# 1-Schematic_petdaktil.net
KiCad netlist of a schematic drawn in EasyEDA
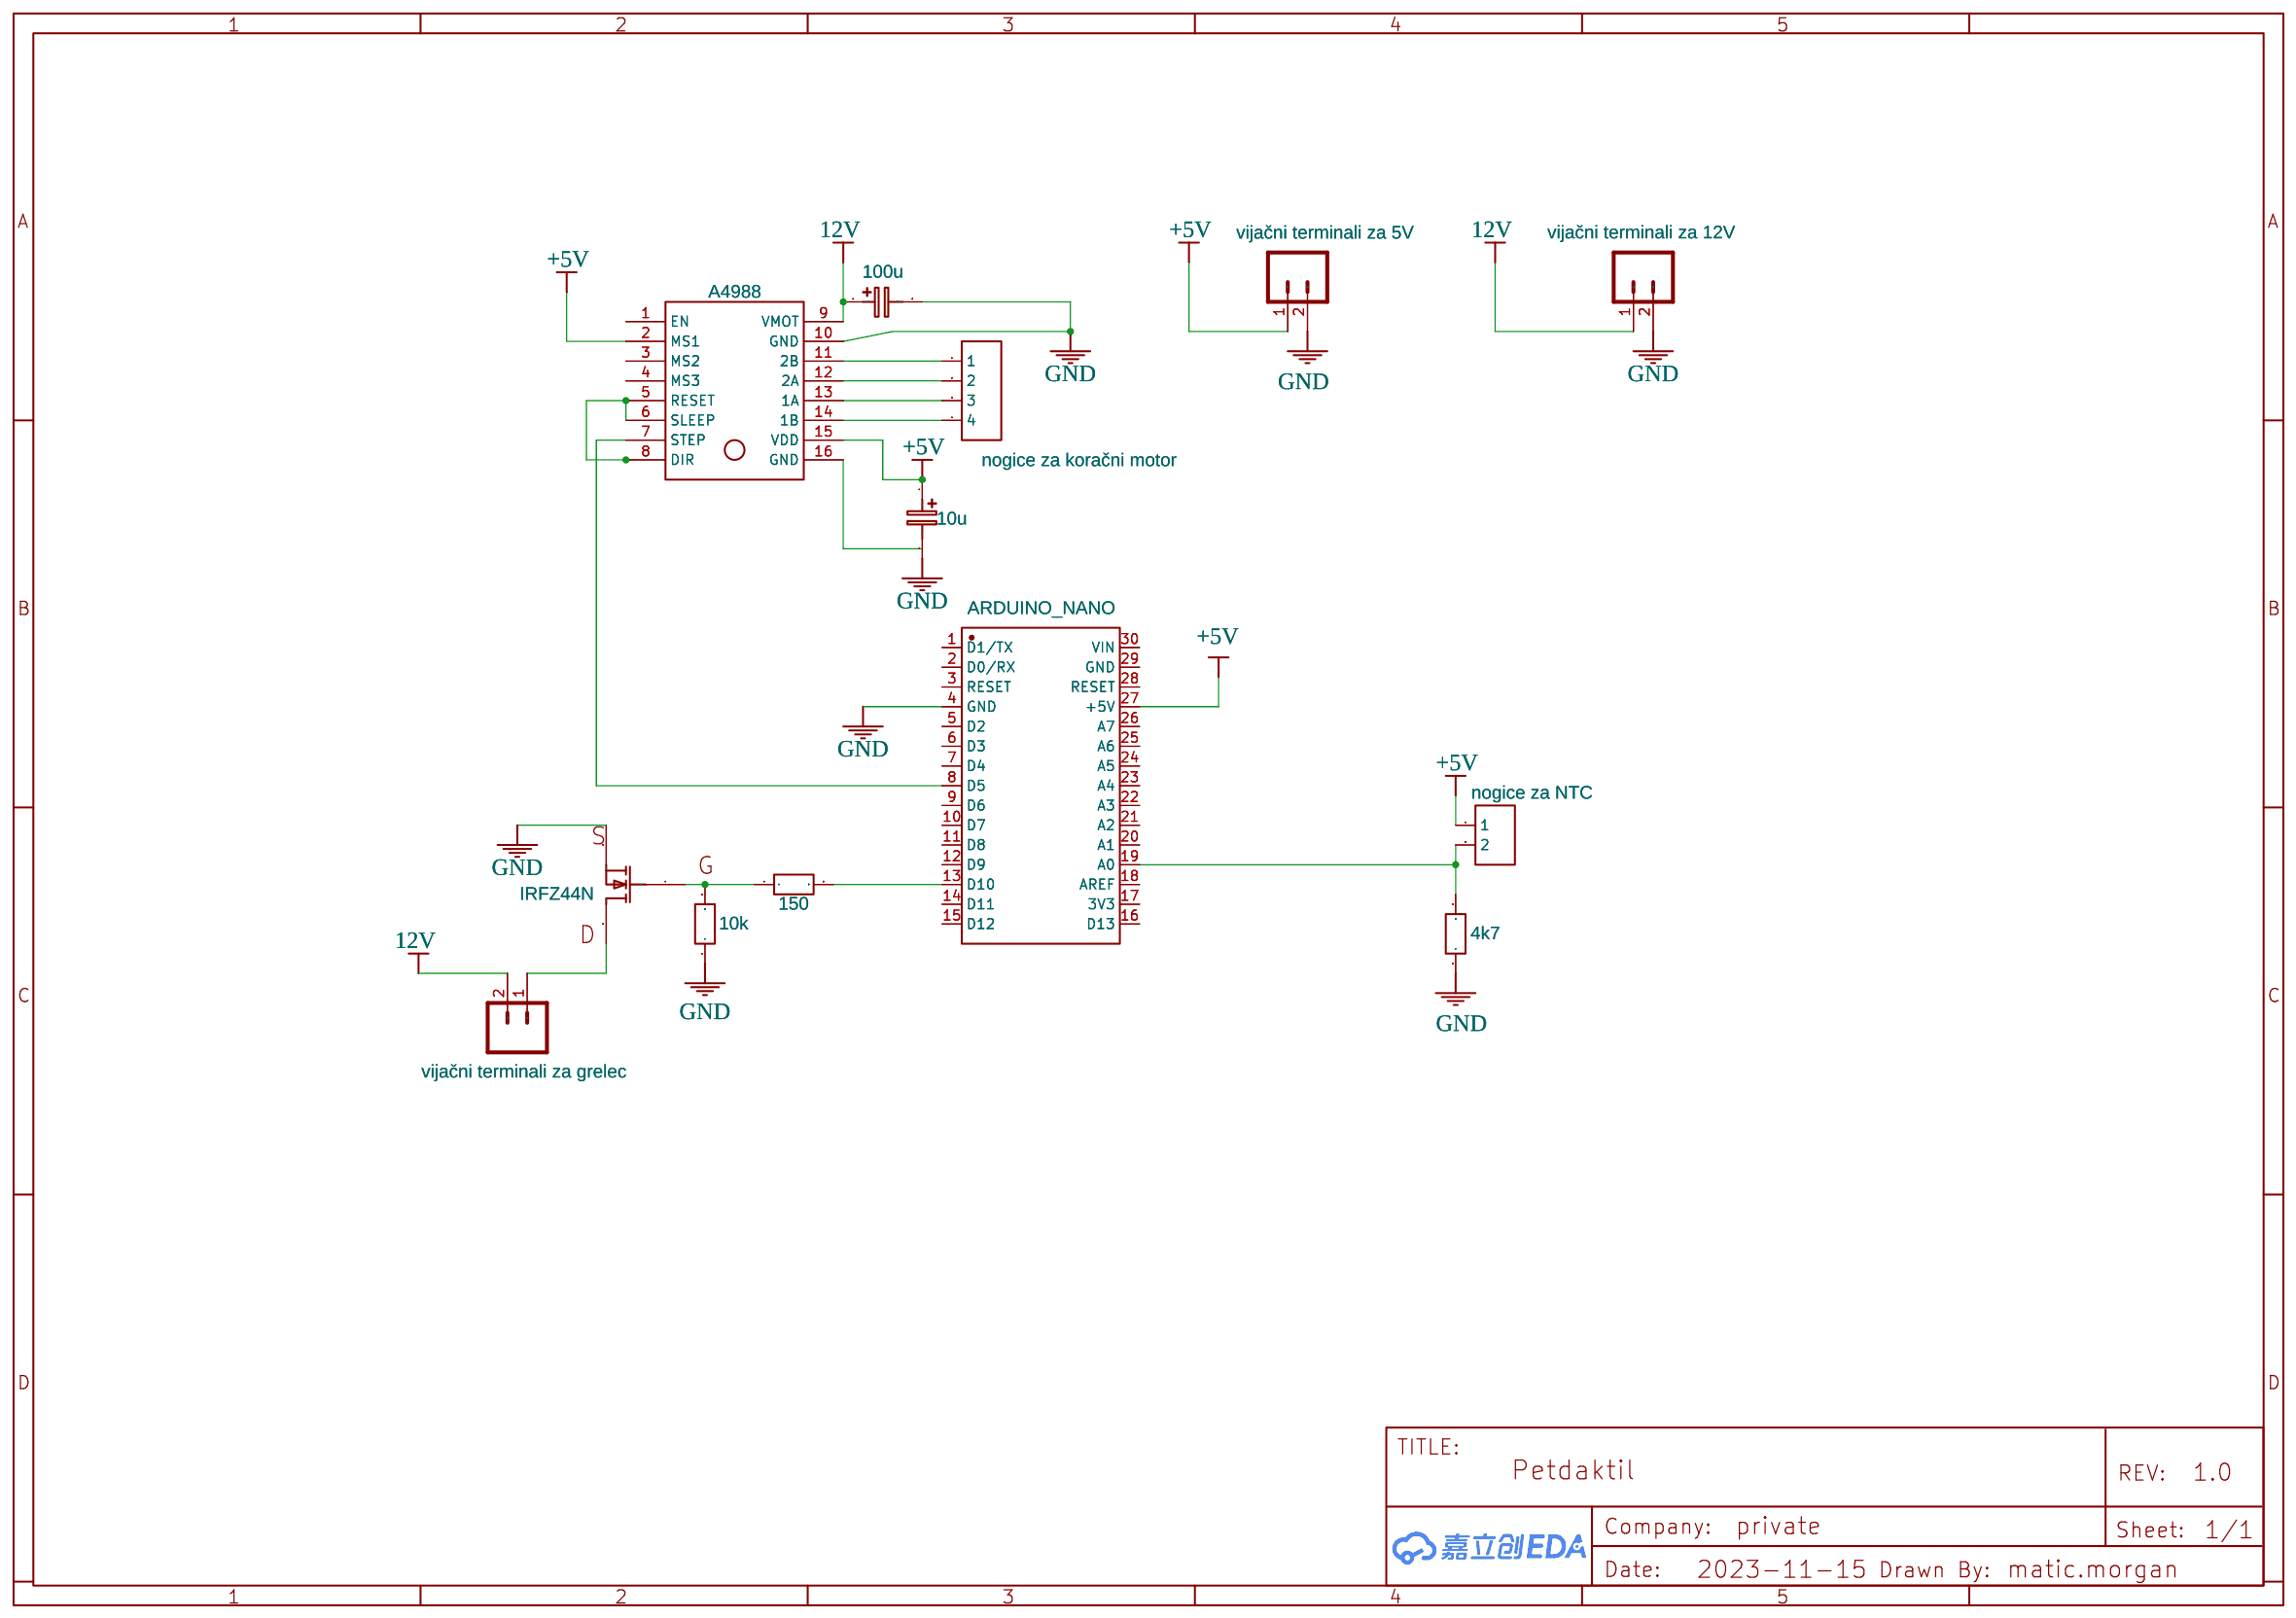
[diagram p0: schematic sheet]

(export (version "E")
  (design (tool "Eeschema 10.0.6"))
  (components
    (comp (ref "C11") (value "100u") (libsource (lib "") (part "CE_TH_D8.0×F3.5_EU")))
    (comp (ref "C21") (value "10u") (libsource (lib "") (part "CE_TH_D5.0×F2.0_EU")))
    (comp (ref "H11") (value "nogice za NTC") (libsource (lib "") (part "HDR-F-2.54_1x2")))
    (comp (ref "J11") (value "nogice za koračni motor") (libsource (lib "") (part "HDR-M-2.54_1x4")))
    (comp (ref "JP11") (value "vijačni terminali za grelec") (libsource (lib "") (part "M023.5MM-NO_SILK_1")))
    (comp (ref "JP21") (value "vijačni terminali za 12V") (libsource (lib "") (part "M023.5MM-NO_SILK")))
    (comp (ref "JP31") (value "vijačni terminali za 5V") (libsource (lib "") (part "M023.5MM-NO_SILK")))
    (comp (ref "Q11") (value "IRFZ44N") (libsource (lib "") (part "IRFZ44N COPY")))
    (comp (ref "R11") (value "150") (libsource (lib "") (part "R_AXIAL-0.3_EU_1")))
    (comp (ref "R21") (value "4k7") (libsource (lib "") (part "R_AXIAL-0.3_EU")))
    (comp (ref "R31") (value "10k") (libsource (lib "") (part "R_AXIAL-0.3_EU")))
    (comp (ref "U1") (value "ARDUINO_NANO") (libsource (lib "") (part "ARDUINO_NANO")))
    (comp (ref "U11")
      (value "A4988")
      (fields (field (name "Manufacturer Part") "ДРАЙВЕР ДВИГАТЕЛЯ A4988"))
      (libsource (lib "") (part "ДРАЙВЕР ДВИГАТЕЛЯ A4988 COPY COPY"))
    )
  )
  (nets
    (net (code "1") (name "+5V") (class "Default")
      (node (ref "C21") (pin "1") (pinfunction "1_1") (pintype "unspecified"))
      (node (ref "H11") (pin "1") (pinfunction "1_1") (pintype "input"))
      (node (ref "JP31") (pin "1") (pinfunction "1_1") (pintype "unspecified"))
      (node (ref "U1") (pin "27") (pinfunction "+5V_27") (pintype "unspecified"))
      (node (ref "U11") (pin "15") (pinfunction "VDD_15") (pintype "unspecified"))
      (node (ref "U11") (pin "2") (pinfunction "MS1_2") (pintype "unspecified"))
    )
    (net (code "2") (name "12V") (class "Default")
      (node (ref "C11") (pin "1") (pinfunction "1_1") (pintype "unspecified"))
      (node (ref "JP11") (pin "2") (pinfunction "2_2") (pintype "unspecified"))
      (node (ref "JP21") (pin "1") (pinfunction "1_1") (pintype "unspecified"))
      (node (ref "U11") (pin "9") (pinfunction "VMOT_9") (pintype "unspecified"))
    )
    (net (code "3") (name "GND") (class "Default")
      (node (ref "C11") (pin "2") (pinfunction "2_2") (pintype "unspecified"))
      (node (ref "C21") (pin "2") (pinfunction "2_2") (pintype "unspecified"))
      (node (ref "JP21") (pin "2") (pinfunction "2_2") (pintype "unspecified"))
      (node (ref "JP31") (pin "2") (pinfunction "2_2") (pintype "unspecified"))
      (node (ref "Q11") (pin "3") (pinfunction "S_3") (pintype "unspecified"))
      (node (ref "R21") (pin "1") (pinfunction "1_1") (pintype "unspecified"))
      (node (ref "R31") (pin "1") (pinfunction "1_1") (pintype "unspecified"))
      (node (ref "U1") (pin "4") (pinfunction "GND_4") (pintype "unspecified"))
      (node (ref "U11") (pin "10") (pinfunction "GND_10") (pintype "unspecified"))
    )
    (net (code "4") (name "Net-(Q11-D)") (class "Default")
      (node (ref "JP11") (pin "1") (pinfunction "1_1") (pintype "unspecified"))
      (node (ref "Q11") (pin "2") (pinfunction "D_2") (pintype "unspecified"))
    )
    (net (code "5") (name "Net-(Q11-G)") (class "Default")
      (node (ref "Q11") (pin "1") (pinfunction "G_1") (pintype "unspecified"))
      (node (ref "R11") (pin "1") (pinfunction "1_1") (pintype "unspecified"))
      (node (ref "R31") (pin "2") (pinfunction "2_2") (pintype "unspecified"))
    )
    (net (code "6") (name "Net-(U1-A0)") (class "Default")
      (node (ref "H11") (pin "2") (pinfunction "2_2") (pintype "input"))
      (node (ref "R21") (pin "2") (pinfunction "2_2") (pintype "unspecified"))
      (node (ref "U1") (pin "19") (pinfunction "A0_19") (pintype "unspecified"))
    )
    (net (code "7") (name "Net-(U1-D5)") (class "Default")
      (node (ref "U1") (pin "8") (pinfunction "D5_8") (pintype "unspecified"))
      (node (ref "U11") (pin "7") (pinfunction "STEP_7") (pintype "unspecified"))
    )
    (net (code "8") (name "Net-(U1-D10)") (class "Default")
      (node (ref "R11") (pin "2") (pinfunction "2_2") (pintype "unspecified"))
      (node (ref "U1") (pin "13") (pinfunction "D10_13") (pintype "unspecified"))
    )
    (net (code "9") (name "Net-(U11-1A)") (class "Default")
      (node (ref "J11") (pin "3") (pinfunction "3_3") (pintype "unspecified"))
      (node (ref "U11") (pin "13") (pinfunction "1A_13") (pintype "unspecified"))
    )
    (net (code "10") (name "Net-(U11-1B)") (class "Default")
      (node (ref "J11") (pin "4") (pinfunction "4_4") (pintype "unspecified"))
      (node (ref "U11") (pin "14") (pinfunction "1B_14") (pintype "unspecified"))
    )
    (net (code "11") (name "Net-(U11-2A)") (class "Default")
      (node (ref "J11") (pin "2") (pinfunction "2_2") (pintype "unspecified"))
      (node (ref "U11") (pin "12") (pinfunction "2A_12") (pintype "unspecified"))
    )
    (net (code "12") (name "Net-(U11-2B)") (class "Default")
      (node (ref "J11") (pin "1") (pinfunction "1_1") (pintype "unspecified"))
      (node (ref "U11") (pin "11") (pinfunction "2B_11") (pintype "unspecified"))
    )
    (net (code "13") (name "Net-(U11-DIR)") (class "Default")
      (node (ref "U11") (pin "5") (pinfunction "RESET_5") (pintype "unspecified"))
      (node (ref "U11") (pin "6") (pinfunction "SLEEP_6") (pintype "unspecified"))
      (node (ref "U11") (pin "8") (pinfunction "DIR_8") (pintype "unspecified"))
    )
    (net (code "14") (name "unconnected-(U1-3V3-Pad17)") (class "Default")
      (node (ref "U1") (pin "17") (pinfunction "3V3_17") (pintype "unspecified"))
    )
    (net (code "15") (name "unconnected-(U1-A1-Pad20)") (class "Default")
      (node (ref "U1") (pin "20") (pinfunction "A1_20") (pintype "unspecified"))
    )
    (net (code "16") (name "unconnected-(U1-A2-Pad21)") (class "Default")
      (node (ref "U1") (pin "21") (pinfunction "A2_21") (pintype "unspecified"))
    )
    (net (code "17") (name "unconnected-(U1-A3-Pad22)") (class "Default")
      (node (ref "U1") (pin "22") (pinfunction "A3_22") (pintype "unspecified"))
    )
    (net (code "18") (name "unconnected-(U1-A4-Pad23)") (class "Default")
      (node (ref "U1") (pin "23") (pinfunction "A4_23") (pintype "unspecified"))
    )
    (net (code "19") (name "unconnected-(U1-A5-Pad24)") (class "Default")
      (node (ref "U1") (pin "24") (pinfunction "A5_24") (pintype "unspecified"))
    )
    (net (code "20") (name "unconnected-(U1-A6-Pad25)") (class "Default")
      (node (ref "U1") (pin "25") (pinfunction "A6_25") (pintype "unspecified"))
    )
    (net (code "21") (name "unconnected-(U1-A7-Pad26)") (class "Default")
      (node (ref "U1") (pin "26") (pinfunction "A7_26") (pintype "unspecified"))
    )
    (net (code "22") (name "unconnected-(U1-AREF-Pad18)") (class "Default")
      (node (ref "U1") (pin "18") (pinfunction "AREF_18") (pintype "unspecified"))
    )
    (net (code "23") (name "unconnected-(U1-D0{slash}RX-Pad2)") (class "Default")
      (node (ref "U1") (pin "2") (pinfunction "D0/RX_2") (pintype "unspecified"))
    )
    (net (code "24") (name "unconnected-(U1-D1{slash}TX-Pad1)") (class "Default")
      (node (ref "U1") (pin "1") (pinfunction "D1/TX_1") (pintype "unspecified"))
    )
    (net (code "25") (name "unconnected-(U1-D2-Pad5)") (class "Default")
      (node (ref "U1") (pin "5") (pinfunction "D2_5") (pintype "unspecified"))
    )
    (net (code "26") (name "unconnected-(U1-D3-Pad6)") (class "Default")
      (node (ref "U1") (pin "6") (pinfunction "D3_6") (pintype "unspecified"))
    )
    (net (code "27") (name "unconnected-(U1-D4-Pad7)") (class "Default")
      (node (ref "U1") (pin "7") (pinfunction "D4_7") (pintype "unspecified"))
    )
    (net (code "28") (name "unconnected-(U1-D6-Pad9)") (class "Default")
      (node (ref "U1") (pin "9") (pinfunction "D6_9") (pintype "unspecified"))
    )
    (net (code "29") (name "unconnected-(U1-D7-Pad10)") (class "Default")
      (node (ref "U1") (pin "10") (pinfunction "D7_10") (pintype "unspecified"))
    )
    (net (code "30") (name "unconnected-(U1-D8-Pad11)") (class "Default")
      (node (ref "U1") (pin "11") (pinfunction "D8_11") (pintype "unspecified"))
    )
    (net (code "31") (name "unconnected-(U1-D9-Pad12)") (class "Default")
      (node (ref "U1") (pin "12") (pinfunction "D9_12") (pintype "unspecified"))
    )
    (net (code "32") (name "unconnected-(U1-D11-Pad14)") (class "Default")
      (node (ref "U1") (pin "14") (pinfunction "D11_14") (pintype "unspecified"))
    )
    (net (code "33") (name "unconnected-(U1-D12-Pad15)") (class "Default")
      (node (ref "U1") (pin "15") (pinfunction "D12_15") (pintype "unspecified"))
    )
    (net (code "34") (name "unconnected-(U1-D13-Pad16)") (class "Default")
      (node (ref "U1") (pin "16") (pinfunction "D13_16") (pintype "unspecified"))
    )
    (net (code "35") (name "unconnected-(U1-GND-Pad29)") (class "Default")
      (node (ref "U1") (pin "29") (pinfunction "GND_29") (pintype "unspecified"))
    )
    (net (code "36") (name "unconnected-(U1-RESET-Pad3)") (class "Default")
      (node (ref "U1") (pin "3") (pinfunction "RESET_3") (pintype "unspecified"))
    )
    (net (code "37") (name "unconnected-(U1-RESET-Pad28)") (class "Default")
      (node (ref "U1") (pin "28") (pinfunction "RESET_28") (pintype "unspecified"))
    )
    (net (code "38") (name "unconnected-(U1-VIN-Pad30)") (class "Default")
      (node (ref "U1") (pin "30") (pinfunction "VIN_30") (pintype "unspecified"))
    )
    (net (code "39") (name "unconnected-(U11-EN-Pad1)") (class "Default")
      (node (ref "U11") (pin "1") (pinfunction "EN_1") (pintype "unspecified"))
    )
    (net (code "40") (name "unconnected-(U11-GND-Pad16)") (class "Default")
      (node (ref "U11") (pin "16") (pinfunction "GND_16") (pintype "unspecified"))
    )
    (net (code "41") (name "unconnected-(U11-MS2-Pad3)") (class "Default")
      (node (ref "U11") (pin "3") (pinfunction "MS2_3") (pintype "unspecified"))
    )
    (net (code "42") (name "unconnected-(U11-MS3-Pad4)") (class "Default")
      (node (ref "U11") (pin "4") (pinfunction "MS3_4") (pintype "unspecified"))
    )
  )
)
